# Switches.net
KiCad netlist of a schematic drawn in Altium Designer
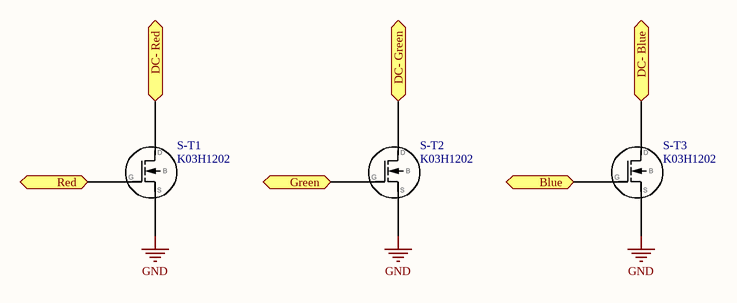
[diagram p0: Switches.SchDoc]

(export (version "E")
  (design (tool "Eeschema 10.0.6"))
  (components
    (comp (ref "S-T1")
      (value "K03H1202")
      (footprint "TO-220-AB")
      (description "Enhancement Type")
      (libsource (lib "ICs") (part "FET N-Channel"))
    )
    (comp (ref "S-T2")
      (value "K03H1202")
      (footprint "TO-220-AB")
      (description "Enhancement Type")
      (libsource (lib "ICs") (part "FET N-Channel"))
    )
    (comp (ref "S-T3")
      (value "K03H1202")
      (footprint "TO-220-AB")
      (description "Enhancement Type")
      (libsource (lib "ICs") (part "FET N-Channel"))
    )
  )
  (nets
    (net (code "1") (name "/Blue") (class "Default")
      (node (ref "S-T3") (pin "G") (pinfunction "G_G") (pintype "passive"))
    )
    (net (code "2") (name "/DC- Blue") (class "Default")
      (node (ref "S-T3") (pin "D") (pinfunction "D_D") (pintype "passive"))
    )
    (net (code "3") (name "/DC- Green") (class "Default")
      (node (ref "S-T2") (pin "D") (pinfunction "D_D") (pintype "passive"))
    )
    (net (code "4") (name "/DC- Red") (class "Default")
      (node (ref "S-T1") (pin "D") (pinfunction "D_D") (pintype "passive"))
    )
    (net (code "5") (name "/Green") (class "Default")
      (node (ref "S-T2") (pin "G") (pinfunction "G_G") (pintype "passive"))
    )
    (net (code "6") (name "/Red") (class "Default")
      (node (ref "S-T1") (pin "G") (pinfunction "G_G") (pintype "passive"))
    )
    (net (code "7") (name "GND") (class "Default")
      (node (ref "S-T1") (pin "S") (pinfunction "S_S") (pintype "passive"))
      (node (ref "S-T2") (pin "S") (pinfunction "S_S") (pintype "passive"))
      (node (ref "S-T3") (pin "S") (pinfunction "S_S") (pintype "passive"))
    )
  )
)
